# rapidshark-dart-detector-mk-1_2.net
KiCad netlist of a schematic drawn in EAGLE
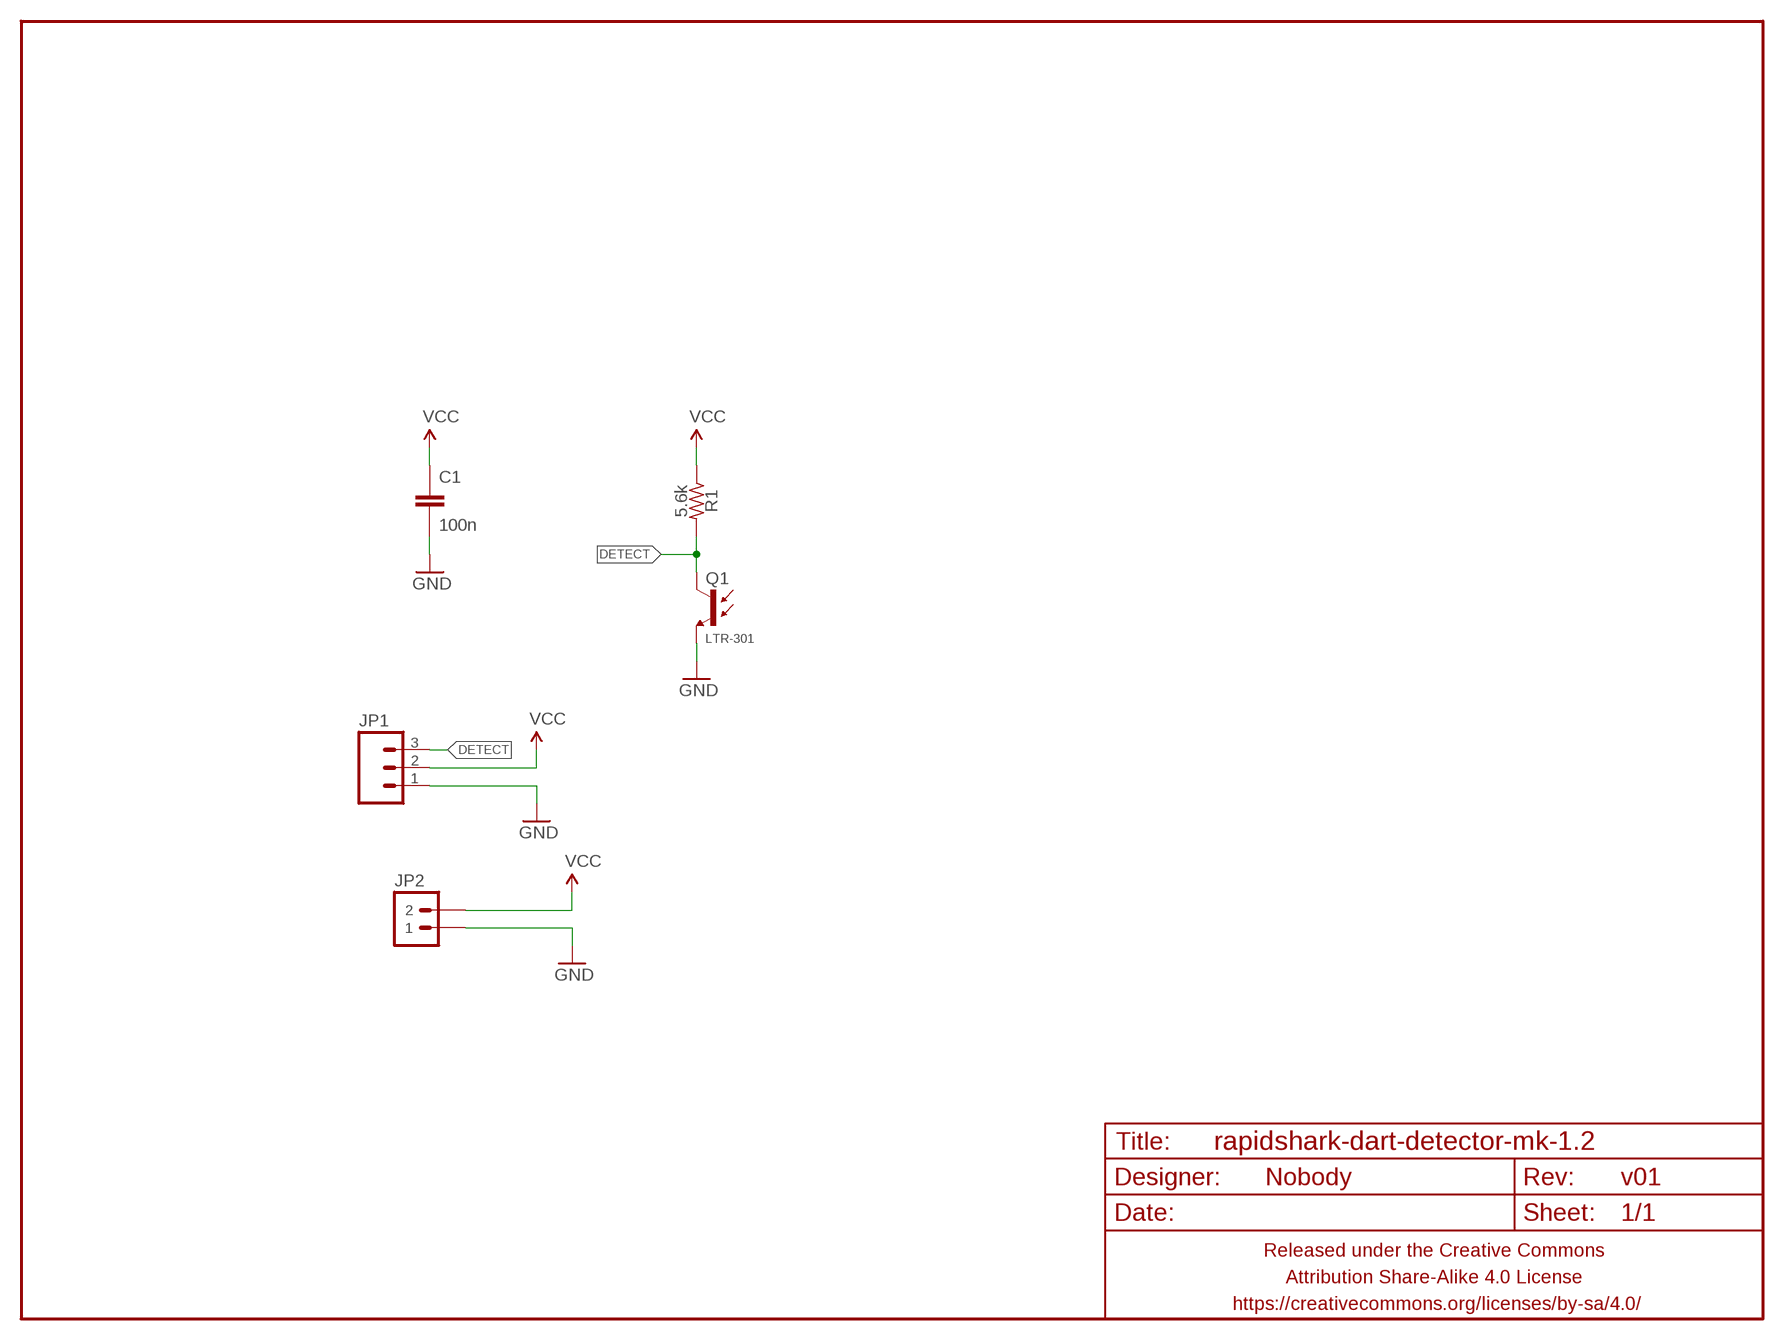
[diagram p0: schematic, sheet 1]

(export (version "E")
  (design (tool "Eeschema 10.0.6"))
  (components
    (comp (ref "C1")
      (value "100n")
      (footprint "eagle-import:C025-024X044")
      (libsource (lib "eagle-import") (part "CAPACITOR-CERAMIC025-024X044"))
    )
    (comp (ref "FRAME1")
      (value "FRAME-LETTERNO_PACKAGE")
      (footprint "eagle-import:DUMMY")
      (fields (field (name "DESIGNER") "Nobody"))
      (libsource (lib "eagle-import") (part "FRAME-LETTERNO_PACKAGE"))
    )
    (comp (ref "JP1")
      (value "M03JST-PTH")
      (footprint "eagle-import:JST-3-PH-RA-PTH")
      (libsource (lib "eagle-import") (part "M03JST-PTH"))
    )
    (comp (ref "JP2")
      (value "M02JST-PTH-RA-R+")
      (footprint "eagle-import:JST-2-PH-RA-PTH-R+")
      (libsource (lib "eagle-import") (part "M02JST-PTH-RA-R+"))
    )
    (comp (ref "Q1")
      (value "LTR-301")
      (footprint "eagle-import:LED-2.54MM-SIDE")
      (libsource (lib "eagle-import") (part "PHOTOTRANSISTOR2.54MM-SIDE"))
    )
    (comp (ref "R1")
      (value "5.6k")
      (footprint "eagle-import:RESISTOR-AXIAL-PTH-5.08MM")
      (libsource (lib "eagle-import") (part "RESISTORPTH-AXIAL-5.08MM"))
    )
  )
  (nets
    (net (code "1") (name "DETECT") (class "Default")
      (node (ref "JP1") (pin "3") (pinfunction "3_3") (pintype "passive"))
      (node (ref "Q1") (pin "A") (pinfunction "C_A") (pintype "bidirectional"))
      (node (ref "R1") (pin "P$2") (pinfunction "2_P$2") (pintype "passive"))
    )
    (net (code "2") (name "GND") (class "Default")
      (node (ref "C1") (pin "2") (pinfunction "2_2") (pintype "passive"))
      (node (ref "JP1") (pin "1") (pinfunction "1_1") (pintype "passive"))
      (node (ref "JP2") (pin "1") (pinfunction "1_1") (pintype "passive"))
      (node (ref "Q1") (pin "K") (pinfunction "E_K") (pintype "bidirectional"))
    )
    (net (code "3") (name "VCC") (class "Default")
      (node (ref "C1") (pin "1") (pinfunction "1_1") (pintype "passive"))
      (node (ref "JP1") (pin "2") (pinfunction "2_2") (pintype "passive"))
      (node (ref "JP2") (pin "2") (pinfunction "2_2") (pintype "passive"))
      (node (ref "R1") (pin "P$1") (pinfunction "1_P$1") (pintype "passive"))
    )
  )
)
